# preamp.net
KiCad netlist of a schematic drawn in EAGLE
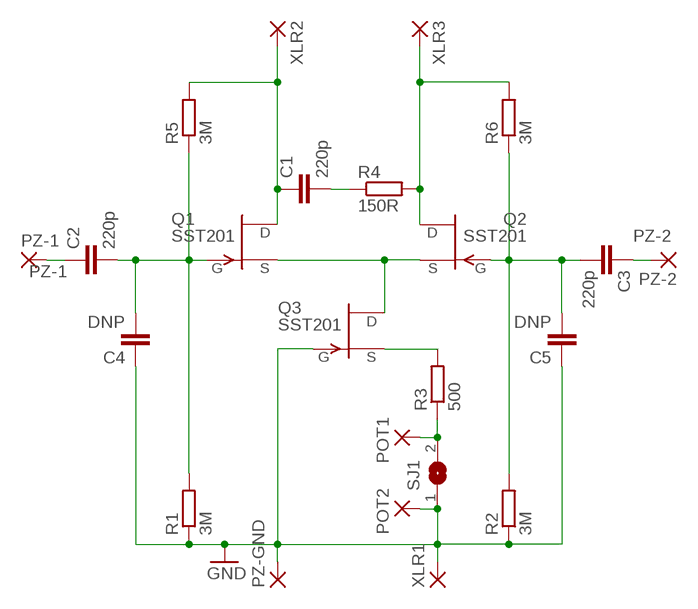
[diagram p0: schematic, sheet 1]

(export (version "E")
  (design (tool "Eeschema 10.0.6"))
  (components
    (comp (ref "C1")
      (value "220p")
      (footprint "eagle-import:C1206")
      (libsource (lib "eagle-import") (part "C-EUC1206"))
    )
    (comp (ref "C2")
      (value "220p")
      (footprint "eagle-import:C1206")
      (libsource (lib "eagle-import") (part "C-EUC1206"))
    )
    (comp (ref "C3")
      (value "220p")
      (footprint "eagle-import:C1206")
      (libsource (lib "eagle-import") (part "C-EUC1206"))
    )
    (comp (ref "C4")
      (value "DNP")
      (footprint "eagle-import:C1206")
      (libsource (lib "eagle-import") (part "C-EUC1206"))
    )
    (comp (ref "C5")
      (value "DNP")
      (footprint "eagle-import:C1206")
      (libsource (lib "eagle-import") (part "C-EUC1206"))
    )
    (comp (ref "POT1")
      (value "3,17/1,3")
      (footprint "eagle-import:3,17_1,3")
      (libsource (lib "eagle-import") (part "3,17/1,3"))
    )
    (comp (ref "POT2")
      (value "3,17/1,3")
      (footprint "eagle-import:3,17_1,3")
      (libsource (lib "eagle-import") (part "3,17/1,3"))
    )
    (comp (ref "PZ-1")
      (value "3,17/1,3")
      (footprint "eagle-import:3,17_1,3")
      (libsource (lib "eagle-import") (part "3,17/1,3"))
    )
    (comp (ref "PZ-2")
      (value "3,17/1,3")
      (footprint "eagle-import:3,17_1,3")
      (libsource (lib "eagle-import") (part "3,17/1,3"))
    )
    (comp (ref "PZ-GND")
      (value "3,17/1,3")
      (footprint "eagle-import:3,17_1,3")
      (libsource (lib "eagle-import") (part "3,17/1,3"))
    )
    (comp (ref "Q1")
      (value "SST201")
      (footprint "eagle-import:SOT23")
      (libsource (lib "eagle-import") (part "?20SST1"))
    )
    (comp (ref "Q2")
      (value "SST201")
      (footprint "eagle-import:SOT23")
      (libsource (lib "eagle-import") (part "?20SST1"))
    )
    (comp (ref "Q3")
      (value "SST201")
      (footprint "eagle-import:SOT23")
      (libsource (lib "eagle-import") (part "?20SST1"))
    )
    (comp (ref "R1")
      (value "3M")
      (footprint "eagle-import:R1206")
      (libsource (lib "eagle-import") (part "R-EU_R1206"))
    )
    (comp (ref "R2")
      (value "3M")
      (footprint "eagle-import:R1206")
      (libsource (lib "eagle-import") (part "R-EU_R1206"))
    )
    (comp (ref "R3")
      (value "500")
      (footprint "eagle-import:R1206")
      (libsource (lib "eagle-import") (part "R-EU_R1206"))
    )
    (comp (ref "R4")
      (value "150R")
      (footprint "eagle-import:R1206")
      (libsource (lib "eagle-import") (part "R-EU_R1206"))
    )
    (comp (ref "R5")
      (value "3M")
      (footprint "eagle-import:R1206")
      (libsource (lib "eagle-import") (part "R-EU_R1206"))
    )
    (comp (ref "R6")
      (value "3M")
      (footprint "eagle-import:R1206")
      (libsource (lib "eagle-import") (part "R-EU_R1206"))
    )
    (comp (ref "SJ1") (value "SJ") (footprint "eagle-import:SJ") (libsource (lib "eagle-import") (part "SJ")))
    (comp (ref "XLR1")
      (value "3,17/1,3")
      (footprint "eagle-import:3,17_1,3")
      (libsource (lib "eagle-import") (part "3,17/1,3"))
    )
    (comp (ref "XLR2")
      (value "3,17/1,3")
      (footprint "eagle-import:3,17_1,3")
      (libsource (lib "eagle-import") (part "3,17/1,3"))
    )
    (comp (ref "XLR3")
      (value "3,17/1,3")
      (footprint "eagle-import:3,17_1,3")
      (libsource (lib "eagle-import") (part "3,17/1,3"))
    )
  )
  (nets
    (net (code "1") (name "/PZ-1") (class "Default")
      (node (ref "C2") (pin "1") (pinfunction "1_1") (pintype "passive"))
      (node (ref "PZ-1") (pin "1") (pinfunction "P_1") (pintype "passive"))
    )
    (net (code "2") (name "/PZ-2") (class "Default")
      (node (ref "C3") (pin "1") (pinfunction "1_1") (pintype "passive"))
      (node (ref "PZ-2") (pin "1") (pinfunction "P_1") (pintype "passive"))
    )
    (net (code "3") (name "GND") (class "Default")
      (node (ref "C4") (pin "1") (pinfunction "1_1") (pintype "passive"))
      (node (ref "C5") (pin "1") (pinfunction "1_1") (pintype "passive"))
      (node (ref "POT2") (pin "1") (pinfunction "P_1") (pintype "passive"))
      (node (ref "PZ-GND") (pin "1") (pinfunction "P_1") (pintype "passive"))
      (node (ref "Q3") (pin "3") (pinfunction "G_3") (pintype "passive"))
      (node (ref "R1") (pin "1") (pinfunction "1_1") (pintype "passive"))
      (node (ref "R2") (pin "1") (pinfunction "1_1") (pintype "passive"))
      (node (ref "SJ1") (pin "1") (pinfunction "1_1") (pintype "passive"))
      (node (ref "XLR1") (pin "1") (pinfunction "P_1") (pintype "passive"))
    )
    (net (code "4") (name "Net-(C1-Pad2)") (class "Default")
      (node (ref "C1") (pin "2") (pinfunction "2_2") (pintype "passive"))
      (node (ref "R4") (pin "1") (pinfunction "1_1") (pintype "passive"))
    )
    (net (code "5") (name "Net-(POT1-P)") (class "Default")
      (node (ref "POT1") (pin "1") (pinfunction "P_1") (pintype "passive"))
      (node (ref "R3") (pin "1") (pinfunction "1_1") (pintype "passive"))
      (node (ref "SJ1") (pin "2") (pinfunction "2_2") (pintype "passive"))
    )
    (net (code "6") (name "Net-(Q1-D)") (class "Default")
      (node (ref "C1") (pin "1") (pinfunction "1_1") (pintype "passive"))
      (node (ref "Q1") (pin "1") (pinfunction "D_1") (pintype "passive"))
      (node (ref "R5") (pin "2") (pinfunction "2_2") (pintype "passive"))
      (node (ref "XLR2") (pin "1") (pinfunction "P_1") (pintype "passive"))
    )
    (net (code "7") (name "Net-(Q1-G)") (class "Default")
      (node (ref "C2") (pin "2") (pinfunction "2_2") (pintype "passive"))
      (node (ref "C4") (pin "2") (pinfunction "2_2") (pintype "passive"))
      (node (ref "Q1") (pin "3") (pinfunction "G_3") (pintype "passive"))
      (node (ref "R1") (pin "2") (pinfunction "2_2") (pintype "passive"))
      (node (ref "R5") (pin "1") (pinfunction "1_1") (pintype "passive"))
    )
    (net (code "8") (name "Net-(Q1-S)") (class "Default")
      (node (ref "Q1") (pin "2") (pinfunction "S_2") (pintype "passive"))
      (node (ref "Q2") (pin "2") (pinfunction "S_2") (pintype "passive"))
      (node (ref "Q3") (pin "1") (pinfunction "D_1") (pintype "passive"))
    )
    (net (code "9") (name "Net-(Q2-D)") (class "Default")
      (node (ref "Q2") (pin "1") (pinfunction "D_1") (pintype "passive"))
      (node (ref "R4") (pin "2") (pinfunction "2_2") (pintype "passive"))
      (node (ref "R6") (pin "2") (pinfunction "2_2") (pintype "passive"))
      (node (ref "XLR3") (pin "1") (pinfunction "P_1") (pintype "passive"))
    )
    (net (code "10") (name "Net-(Q2-G)") (class "Default")
      (node (ref "C3") (pin "2") (pinfunction "2_2") (pintype "passive"))
      (node (ref "C5") (pin "2") (pinfunction "2_2") (pintype "passive"))
      (node (ref "Q2") (pin "3") (pinfunction "G_3") (pintype "passive"))
      (node (ref "R2") (pin "2") (pinfunction "2_2") (pintype "passive"))
      (node (ref "R6") (pin "1") (pinfunction "1_1") (pintype "passive"))
    )
    (net (code "11") (name "Net-(Q3-S)") (class "Default")
      (node (ref "Q3") (pin "2") (pinfunction "S_2") (pintype "passive"))
      (node (ref "R3") (pin "2") (pinfunction "2_2") (pintype "passive"))
    )
  )
)
